# power.net
KiCad netlist of a schematic drawn in Altium Designer
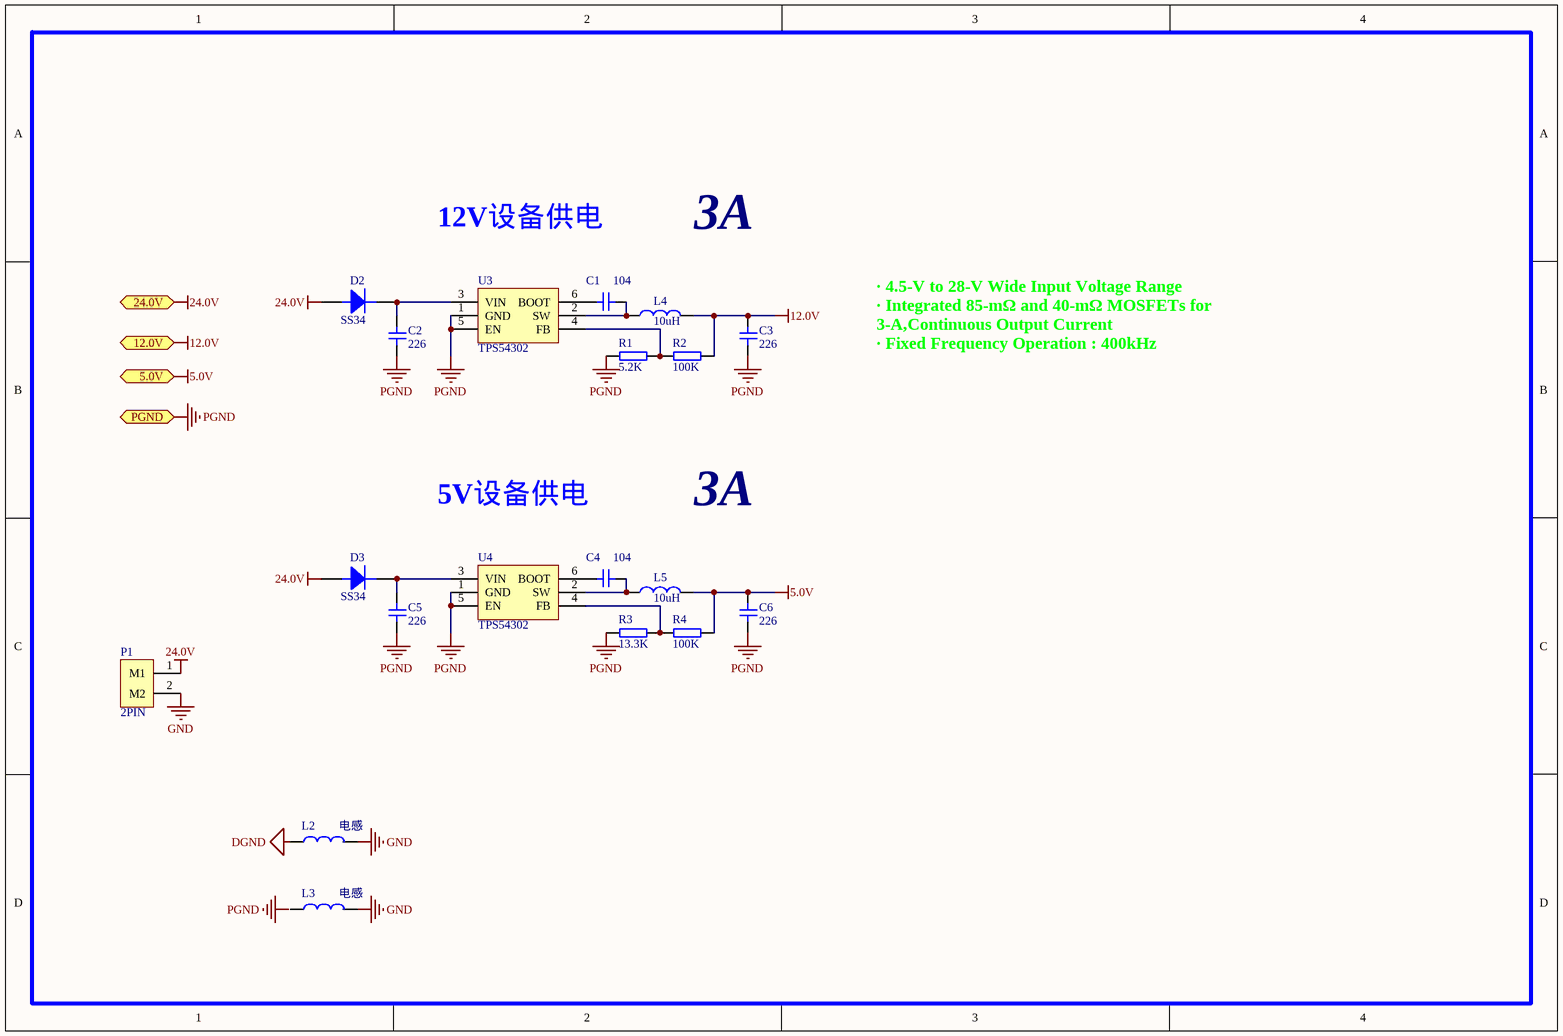
[diagram p0: power.SchDoc]

(export (version "E")
  (design (tool "Eeschema 10.0.6"))
  (components
    (comp (ref "C1")
      (value "104")
      (footprint "0603C")
      (description "无极贴片电容")
      (libsource (lib "集大电协1.5") (part "Cap1"))
    )
    (comp (ref "C2")
      (value "226")
      (footprint "1206C")
      (description "无极贴片电容")
      (libsource (lib "集大电协1.5") (part "Cap1"))
    )
    (comp (ref "C3")
      (value "226")
      (footprint "0603C")
      (description "无极贴片电容")
      (libsource (lib "集大电协1.5") (part "Cap1"))
    )
    (comp (ref "C4")
      (value "104")
      (footprint "0603C")
      (description "无极贴片电容")
      (libsource (lib "集大电协1.5") (part "Cap1"))
    )
    (comp (ref "C5")
      (value "226")
      (footprint "1206C")
      (description "无极贴片电容")
      (libsource (lib "集大电协1.5") (part "Cap1"))
    )
    (comp (ref "C6")
      (value "226")
      (footprint "0603C")
      (description "无极贴片电容")
      (libsource (lib "集大电协1.5") (part "Cap1"))
    )
    (comp (ref "D2")
      (value "SS34")
      (footprint "SMA/DO-214AC")
      (description "二极管")
      (libsource (lib "集大电协1.5") (part "Diode"))
    )
    (comp (ref "D3")
      (value "SS34")
      (footprint "SMA/DO-214AC")
      (description "二极管")
      (libsource (lib "集大电协1.5") (part "Diode"))
    )
    (comp (ref "L2") (value "电感") (footprint "1206L") (libsource (lib "集大电协1.5") (part "L")))
    (comp (ref "L3") (value "电感") (footprint "1206L") (libsource (lib "集大电协1.5") (part "L")))
    (comp (ref "L4")
      (value "10uH")
      (footprint "0630L")
      (description "电感")
      (libsource (lib "集大电协1.5") (part "L"))
    )
    (comp (ref "L5")
      (value "10uH")
      (footprint "0630L")
      (description "电感")
      (libsource (lib "集大电协1.5") (part "L"))
    )
    (comp (ref "P1") (value "2PIN") (footprint "KF350-2P") (libsource (lib "集大电协1.5") (part "接线端子-2PIN")))
    (comp (ref "R1")
      (value "5.2K")
      (footprint "0603R")
      (description "电阻")
      (libsource (lib "集大电协1.5") (part "Res"))
    )
    (comp (ref "R2")
      (value "100K")
      (footprint "0603R")
      (description "电阻")
      (libsource (lib "集大电协1.5") (part "Res"))
    )
    (comp (ref "R3")
      (value "13.3K")
      (footprint "0603R")
      (description "电阻")
      (libsource (lib "集大电协1.5") (part "Res"))
    )
    (comp (ref "R4")
      (value "100K")
      (footprint "0603R")
      (description "电阻")
      (libsource (lib "集大电协1.5") (part "Res"))
    )
    (comp (ref "U3") (value "TPS54302") (footprint "SOT23-6") (libsource (lib "集大电协1.5") (part "TPS54302")))
    (comp (ref "U4") (value "TPS54302") (footprint "SOT23-6") (libsource (lib "集大电协1.5") (part "TPS54302")))
  )
  (nets
    (net (code "1") (name "5.0V") (class "Default")
      (node (ref "C6") (pin "2") (pinfunction "2_2") (pintype "passive"))
      (node (ref "L5") (pin "2") (pinfunction "2_2") (pintype "passive"))
      (node (ref "R4") (pin "1") (pinfunction "1_1") (pintype "passive"))
    )
    (net (code "2") (name "12.0V") (class "Default")
      (node (ref "C3") (pin "2") (pinfunction "2_2") (pintype "passive"))
      (node (ref "L4") (pin "2") (pinfunction "2_2") (pintype "passive"))
      (node (ref "R2") (pin "1") (pinfunction "1_1") (pintype "passive"))
    )
    (net (code "3") (name "24.0V") (class "Default")
      (node (ref "D2") (pin "1") (pintype "passive"))
      (node (ref "D3") (pin "1") (pintype "passive"))
      (node (ref "P1") (pin "1") (pinfunction "M1_1") (pintype "passive"))
    )
    (net (code "4") (name "DGND") (class "Default")
      (node (ref "L2") (pin "1") (pinfunction "1_1") (pintype "passive"))
    )
    (net (code "5") (name "GND") (class "Default")
      (node (ref "L2") (pin "2") (pinfunction "2_2") (pintype "passive"))
      (node (ref "L3") (pin "2") (pinfunction "2_2") (pintype "passive"))
      (node (ref "P1") (pin "2") (pinfunction "M2_2") (pintype "passive"))
    )
    (net (code "6") (name "Net-(U3-BOOT)") (class "Default")
      (node (ref "C1") (pin "2") (pinfunction "2_2") (pintype "passive"))
      (node (ref "U3") (pin "6") (pinfunction "BOOT_6") (pintype "passive"))
    )
    (net (code "7") (name "Net-(U3-FB)") (class "Default")
      (node (ref "R1") (pin "1") (pinfunction "1_1") (pintype "passive"))
      (node (ref "R2") (pin "2") (pinfunction "2_2") (pintype "passive"))
      (node (ref "U3") (pin "4") (pinfunction "FB_4") (pintype "passive"))
    )
    (net (code "8") (name "Net-(U3-SW)") (class "Default")
      (node (ref "C1") (pin "1") (pinfunction "1_1") (pintype "passive"))
      (node (ref "L4") (pin "1") (pinfunction "1_1") (pintype "passive"))
      (node (ref "U3") (pin "2") (pinfunction "SW_2") (pintype "passive"))
    )
    (net (code "9") (name "Net-(U3-VIN)") (class "Default")
      (node (ref "C2") (pin "2") (pinfunction "2_2") (pintype "passive"))
      (node (ref "D2") (pin "2") (pinfunction "2_2") (pintype "passive"))
      (node (ref "U3") (pin "3") (pinfunction "VIN_3") (pintype "passive"))
    )
    (net (code "10") (name "Net-(U4-BOOT)") (class "Default")
      (node (ref "C4") (pin "2") (pinfunction "2_2") (pintype "passive"))
      (node (ref "U4") (pin "6") (pinfunction "BOOT_6") (pintype "passive"))
    )
    (net (code "11") (name "Net-(U4-FB)") (class "Default")
      (node (ref "R3") (pin "1") (pinfunction "1_1") (pintype "passive"))
      (node (ref "R4") (pin "2") (pinfunction "2_2") (pintype "passive"))
      (node (ref "U4") (pin "4") (pinfunction "FB_4") (pintype "passive"))
    )
    (net (code "12") (name "Net-(U4-SW)") (class "Default")
      (node (ref "C4") (pin "1") (pinfunction "1_1") (pintype "passive"))
      (node (ref "L5") (pin "1") (pinfunction "1_1") (pintype "passive"))
      (node (ref "U4") (pin "2") (pinfunction "SW_2") (pintype "passive"))
    )
    (net (code "13") (name "Net-(U4-VIN)") (class "Default")
      (node (ref "C5") (pin "2") (pinfunction "2_2") (pintype "passive"))
      (node (ref "D3") (pin "2") (pinfunction "2_2") (pintype "passive"))
      (node (ref "U4") (pin "3") (pinfunction "VIN_3") (pintype "passive"))
    )
    (net (code "14") (name "PGND") (class "Default")
      (node (ref "C2") (pin "1") (pinfunction "1_1") (pintype "passive"))
      (node (ref "C3") (pin "1") (pinfunction "1_1") (pintype "passive"))
      (node (ref "C5") (pin "1") (pinfunction "1_1") (pintype "passive"))
      (node (ref "C6") (pin "1") (pinfunction "1_1") (pintype "passive"))
      (node (ref "R1") (pin "2") (pinfunction "2_2") (pintype "passive"))
      (node (ref "R3") (pin "2") (pinfunction "2_2") (pintype "passive"))
      (node (ref "U3") (pin "1") (pinfunction "GND_1") (pintype "passive"))
      (node (ref "U3") (pin "5") (pinfunction "EN_5") (pintype "passive"))
      (node (ref "U4") (pin "1") (pinfunction "GND_1") (pintype "passive"))
      (node (ref "U4") (pin "5") (pinfunction "EN_5") (pintype "passive"))
    )
    (net (code "15") (name "unconnected-(L3-Pad1)") (class "Default")
      (node (ref "L3") (pin "1") (pinfunction "1_1") (pintype "passive"))
    )
  )
)
